# bb-8.net
KiCad netlist of a schematic drawn in EAGLE
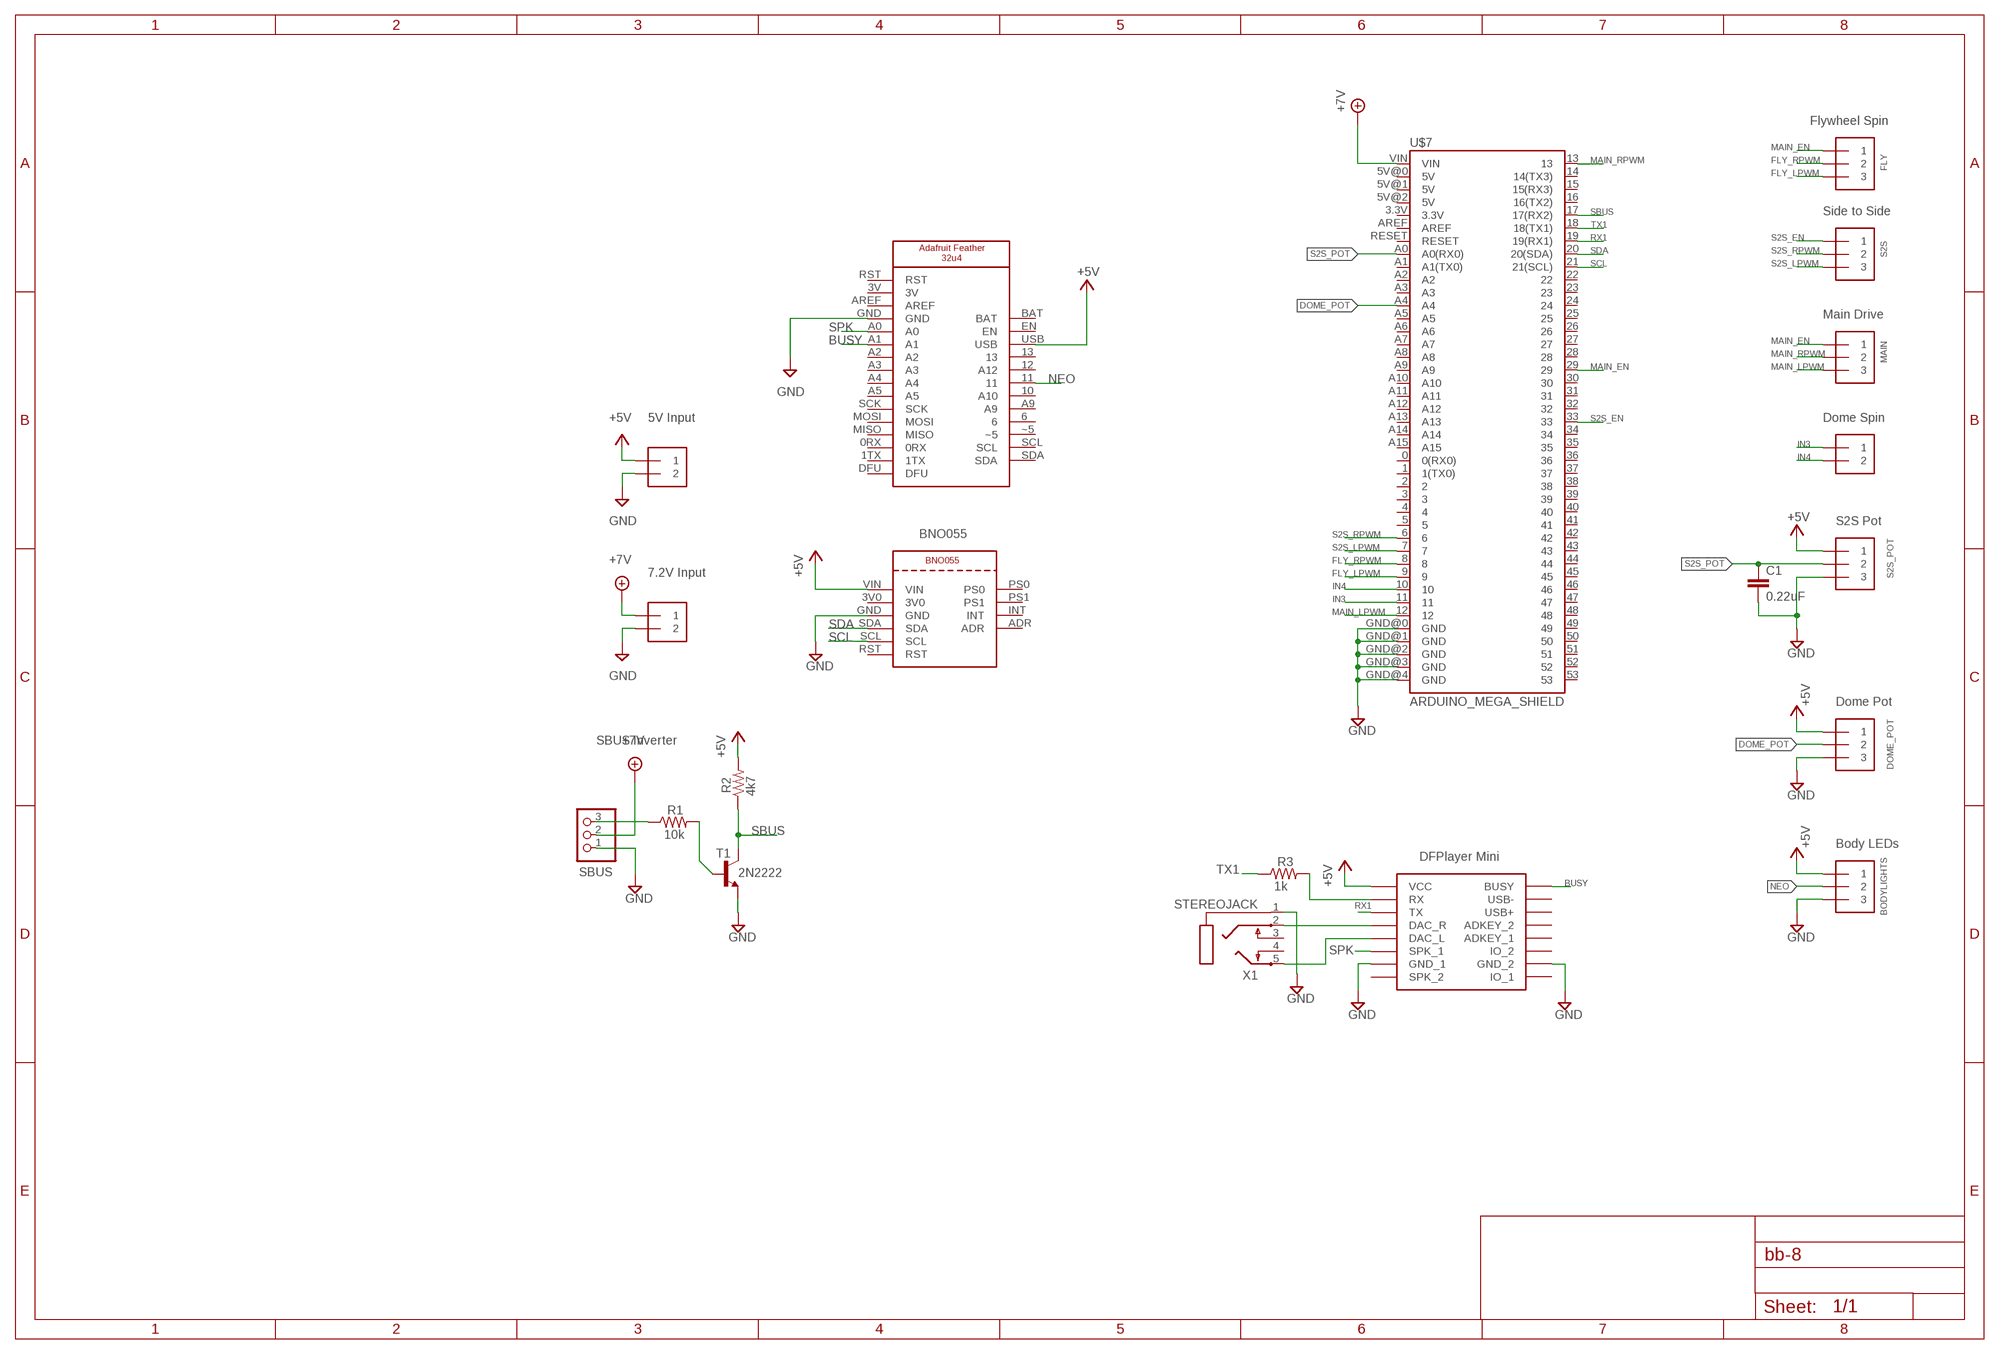
[diagram p0: schematic, sheet 1]

(export (version "E")
  (design (tool "Eeschema 10.0.6"))
  (components
    (comp (ref "5V")
      (value "1X2-3.5MM")
      (footprint "eagle-import:1X2-3.5MM")
      (libsource (lib "eagle-import") (part "1X2-3.5MM"))
    )
    (comp (ref "7V2")
      (value "1X2-3.5MM")
      (footprint "eagle-import:1X2-3.5MM")
      (libsource (lib "eagle-import") (part "1X2-3.5MM"))
    )
    (comp (ref "BODYLIGHTS")
      (value "SCREW_TERMINAL_3_PIN")
      (footprint "eagle-import:SCREW_TERMINAL_3_PIN")
      (libsource (lib "eagle-import") (part "SCREW_TERMINAL_3_PIN"))
    )
    (comp (ref "C1")
      (value "0.22uF")
      (footprint "eagle-import:C050-024X044")
      (libsource (lib "eagle-import") (part "C-EU050-024X044"))
    )
    (comp (ref "DOME")
      (value "1X2-3.5MM")
      (footprint "eagle-import:1X2-3.5MM")
      (libsource (lib "eagle-import") (part "1X2-3.5MM"))
    )
    (comp (ref "DOME_POT")
      (value "SCREW_TERMINAL_3_PIN")
      (footprint "eagle-import:SCREW_TERMINAL_3_PIN")
      (libsource (lib "eagle-import") (part "SCREW_TERMINAL_3_PIN"))
    )
    (comp (ref "FLY")
      (value "SCREW_TERMINAL_3_PIN")
      (footprint "eagle-import:SCREW_TERMINAL_3_PIN")
      (libsource (lib "eagle-import") (part "SCREW_TERMINAL_3_PIN"))
    )
    (comp (ref "MAIN")
      (value "SCREW_TERMINAL_3_PIN")
      (footprint "eagle-import:SCREW_TERMINAL_3_PIN")
      (libsource (lib "eagle-import") (part "SCREW_TERMINAL_3_PIN"))
    )
    (comp (ref "R1")
      (value "10k")
      (footprint "eagle-import:0204_7")
      (libsource (lib "eagle-import") (part "R-US_0204/7"))
    )
    (comp (ref "R2")
      (value "4k7")
      (footprint "eagle-import:0204_7")
      (libsource (lib "eagle-import") (part "R-US_0204/7"))
    )
    (comp (ref "R3")
      (value "1k")
      (footprint "eagle-import:0204_7")
      (libsource (lib "eagle-import") (part "R-US_0204/7"))
    )
    (comp (ref "S2S")
      (value "SCREW_TERMINAL_3_PIN")
      (footprint "eagle-import:SCREW_TERMINAL_3_PIN")
      (libsource (lib "eagle-import") (part "SCREW_TERMINAL_3_PIN"))
    )
    (comp (ref "S2S_POT")
      (value "SCREW_TERMINAL_3_PIN")
      (footprint "eagle-import:SCREW_TERMINAL_3_PIN")
      (libsource (lib "eagle-import") (part "SCREW_TERMINAL_3_PIN"))
    )
    (comp (ref "SBUS")
      (value "PINHD-1X3")
      (footprint "eagle-import:1X03")
      (libsource (lib "eagle-import") (part "PINHD-1X3"))
    )
    (comp (ref "T1")
      (value "2N2222")
      (footprint "eagle-import:TO92-EBC-OVAL")
      (libsource (lib "eagle-import") (part "2N2222"))
    )
    (comp (ref "U$1")
      (value "DFPLAYER")
      (footprint "eagle-import:DFPLAYER")
      (libsource (lib "eagle-import") (part "DFPLAYER"))
    )
    (comp (ref "U$2")
      (value "ADAFRUIT_BNO055")
      (footprint "eagle-import:ADAFRUIT_BNO055")
      (libsource (lib "eagle-import") (part "ADAFRUIT_BNO055"))
    )
    (comp (ref "U$3")
      (value "ADAFRUIT_FEATHER_32U4")
      (footprint "eagle-import:ADAFRUIT_FEATHER_32U4")
      (libsource (lib "eagle-import") (part "ADAFRUIT_FEATHER_32U4"))
    )
    (comp (ref "U$7")
      (value "ARDUINO_MEGA_SHIELD")
      (footprint "eagle-import:ARDUINO_MEGA_SHIELD")
      (libsource (lib "eagle-import") (part "ARDUINO_MEGA_SHIELD"))
    )
    (comp (ref "X1")
      (value "STEREOJACK")
      (footprint "eagle-import:STX3100")
      (libsource (lib "eagle-import") (part "STEREOJACK"))
    )
  )
  (nets
    (net (code "1") (name "+5V") (class "Default")
      (node (ref "5V") (pin "1") (pinfunction "1_1") (pintype "passive"))
      (node (ref "BODYLIGHTS") (pin "1") (pinfunction "1_1") (pintype "bidirectional"))
      (node (ref "DOME_POT") (pin "1") (pinfunction "1_1") (pintype "bidirectional"))
      (node (ref "R2") (pin "2") (pinfunction "2_2") (pintype "passive"))
      (node (ref "S2S_POT") (pin "1") (pinfunction "1_1") (pintype "bidirectional"))
      (node (ref "U$1") (pin "VCC") (pinfunction "VCC_VCC") (pintype "bidirectional"))
      (node (ref "U$2") (pin "VIN") (pinfunction "VIN_VIN") (pintype "bidirectional"))
      (node (ref "U$3") (pin "USB") (pinfunction "USB_USB") (pintype "bidirectional"))
    )
    (net (code "2") (name "+7V") (class "Default")
      (node (ref "7V2") (pin "1") (pinfunction "1_1") (pintype "passive"))
      (node (ref "SBUS") (pin "2") (pinfunction "2_2") (pintype "passive"))
      (node (ref "U$7") (pin "VIN") (pinfunction "VIN_VIN") (pintype "bidirectional"))
    )
    (net (code "3") (name "/BUSY") (class "Default")
      (node (ref "U$1") (pin "BUSY") (pinfunction "BUSY_BUSY") (pintype "bidirectional"))
      (node (ref "U$3") (pin "A1") (pinfunction "A1_A1") (pintype "bidirectional"))
    )
    (net (code "4") (name "/FLY_LPWM") (class "Default")
      (node (ref "FLY") (pin "3") (pinfunction "3_3") (pintype "bidirectional"))
      (node (ref "U$7") (pin "9") (pinfunction "9_9") (pintype "bidirectional"))
    )
    (net (code "5") (name "/FLY_RPWM") (class "Default")
      (node (ref "FLY") (pin "2") (pinfunction "2_2") (pintype "bidirectional"))
      (node (ref "U$7") (pin "8") (pinfunction "8_8") (pintype "bidirectional"))
    )
    (net (code "6") (name "/IN3") (class "Default")
      (node (ref "DOME") (pin "1") (pinfunction "1_1") (pintype "passive"))
      (node (ref "U$7") (pin "11") (pinfunction "11_11") (pintype "bidirectional"))
    )
    (net (code "7") (name "/IN4") (class "Default")
      (node (ref "DOME") (pin "2") (pinfunction "2_2") (pintype "passive"))
      (node (ref "U$7") (pin "10") (pinfunction "10_10") (pintype "bidirectional"))
    )
    (net (code "8") (name "/MAIN_EN") (class "Default")
      (node (ref "FLY") (pin "1") (pinfunction "1_1") (pintype "bidirectional"))
      (node (ref "MAIN") (pin "1") (pinfunction "1_1") (pintype "bidirectional"))
      (node (ref "U$7") (pin "29") (pinfunction "29_29") (pintype "bidirectional"))
    )
    (net (code "9") (name "/MAIN_LPWM") (class "Default")
      (node (ref "MAIN") (pin "3") (pinfunction "3_3") (pintype "bidirectional"))
      (node (ref "U$7") (pin "12") (pinfunction "12_12") (pintype "bidirectional"))
    )
    (net (code "10") (name "/MAIN_RPWM") (class "Default")
      (node (ref "MAIN") (pin "2") (pinfunction "2_2") (pintype "bidirectional"))
      (node (ref "U$7") (pin "13") (pinfunction "13_13") (pintype "bidirectional"))
    )
    (net (code "11") (name "/RX1") (class "Default")
      (node (ref "U$1") (pin "TX") (pinfunction "TX_TX") (pintype "bidirectional"))
      (node (ref "U$7") (pin "19") (pinfunction "19(RX1)_19") (pintype "bidirectional"))
    )
    (net (code "12") (name "/S2S_EN") (class "Default")
      (node (ref "S2S") (pin "1") (pinfunction "1_1") (pintype "bidirectional"))
      (node (ref "U$7") (pin "33") (pinfunction "33_33") (pintype "bidirectional"))
    )
    (net (code "13") (name "/S2S_LPWM") (class "Default")
      (node (ref "S2S") (pin "3") (pinfunction "3_3") (pintype "bidirectional"))
      (node (ref "U$7") (pin "7") (pinfunction "7_7") (pintype "bidirectional"))
    )
    (net (code "14") (name "/S2S_RPWM") (class "Default")
      (node (ref "S2S") (pin "2") (pinfunction "2_2") (pintype "bidirectional"))
      (node (ref "U$7") (pin "6") (pinfunction "6_6") (pintype "bidirectional"))
    )
    (net (code "15") (name "/SBUS") (class "Default")
      (node (ref "R2") (pin "1") (pinfunction "1_1") (pintype "passive"))
      (node (ref "T1") (pin "C") (pinfunction "C_C") (pintype "passive"))
      (node (ref "U$7") (pin "17") (pinfunction "17(RX2)_17") (pintype "bidirectional"))
    )
    (net (code "16") (name "/SCL") (class "Default")
      (node (ref "U$2") (pin "SCL") (pinfunction "SCL_SCL") (pintype "bidirectional"))
      (node (ref "U$7") (pin "21") (pinfunction "21(SCL)_21") (pintype "bidirectional"))
    )
    (net (code "17") (name "/SDA") (class "Default")
      (node (ref "U$2") (pin "SDA") (pinfunction "SDA_SDA") (pintype "bidirectional"))
      (node (ref "U$7") (pin "20") (pinfunction "20(SDA)_20") (pintype "bidirectional"))
    )
    (net (code "18") (name "/SPK") (class "Default")
      (node (ref "U$1") (pin "SPK1") (pinfunction "SPK_1_SPK1") (pintype "bidirectional"))
      (node (ref "U$3") (pin "A0") (pinfunction "A0_A0") (pintype "bidirectional"))
    )
    (net (code "19") (name "/TX1") (class "Default")
      (node (ref "R3") (pin "1") (pinfunction "1_1") (pintype "passive"))
      (node (ref "U$7") (pin "18") (pinfunction "18(TX1)_18") (pintype "bidirectional"))
    )
    (net (code "20") (name "DOME_POT") (class "Default")
      (node (ref "DOME_POT") (pin "2") (pinfunction "2_2") (pintype "bidirectional"))
      (node (ref "U$7") (pin "A4") (pinfunction "A4_A4") (pintype "bidirectional"))
    )
    (net (code "21") (name "GND") (class "Default")
      (node (ref "5V") (pin "2") (pinfunction "2_2") (pintype "passive"))
      (node (ref "7V2") (pin "2") (pinfunction "2_2") (pintype "passive"))
      (node (ref "BODYLIGHTS") (pin "3") (pinfunction "3_3") (pintype "bidirectional"))
      (node (ref "C1") (pin "2") (pinfunction "2_2") (pintype "passive"))
      (node (ref "DOME_POT") (pin "3") (pinfunction "3_3") (pintype "bidirectional"))
      (node (ref "S2S_POT") (pin "3") (pinfunction "3_3") (pintype "bidirectional"))
      (node (ref "SBUS") (pin "1") (pinfunction "1_1") (pintype "passive"))
      (node (ref "T1") (pin "E") (pinfunction "E_E") (pintype "passive"))
      (node (ref "U$1") (pin "GND_1") (pinfunction "GND_1_GND_1") (pintype "bidirectional"))
      (node (ref "U$1") (pin "GND_2") (pinfunction "GND_2_GND_2") (pintype "bidirectional"))
      (node (ref "U$2") (pin "GND") (pinfunction "GND_GND") (pintype "bidirectional"))
      (node (ref "U$3") (pin "GND") (pinfunction "GND_GND") (pintype "bidirectional"))
      (node (ref "U$7") (pin "GND@0") (pinfunction "GND_GND@0") (pintype "bidirectional"))
      (node (ref "U$7") (pin "GND@1") (pinfunction "GND_GND@1") (pintype "bidirectional"))
      (node (ref "U$7") (pin "GND@2") (pinfunction "GND_GND@2") (pintype "bidirectional"))
      (node (ref "U$7") (pin "GND@3") (pinfunction "GND_GND@3") (pintype "bidirectional"))
      (node (ref "U$7") (pin "GND@4") (pinfunction "GND_GND@4") (pintype "bidirectional"))
      (node (ref "X1") (pin "1") (pinfunction "1_1") (pintype "passive"))
    )
    (net (code "22") (name "NEO") (class "Default")
      (node (ref "BODYLIGHTS") (pin "2") (pinfunction "2_2") (pintype "bidirectional"))
      (node (ref "U$3") (pin "11") (pinfunction "11_11") (pintype "bidirectional"))
    )
    (net (code "23") (name "Net-(R1-Pad1)") (class "Default")
      (node (ref "R1") (pin "1") (pinfunction "1_1") (pintype "passive"))
      (node (ref "SBUS") (pin "3") (pinfunction "3_3") (pintype "passive"))
    )
    (net (code "24") (name "Net-(R1-Pad2)") (class "Default")
      (node (ref "R1") (pin "2") (pinfunction "2_2") (pintype "passive"))
      (node (ref "T1") (pin "B") (pinfunction "B_B") (pintype "passive"))
    )
    (net (code "25") (name "Net-(R3-Pad2)") (class "Default")
      (node (ref "R3") (pin "2") (pinfunction "2_2") (pintype "passive"))
      (node (ref "U$1") (pin "RX") (pinfunction "RX_RX") (pintype "bidirectional"))
    )
    (net (code "26") (name "Net-(U$1-PadDAC_L)") (class "Default")
      (node (ref "U$1") (pin "DAC_L") (pinfunction "DAC_L_DAC_L") (pintype "bidirectional"))
      (node (ref "X1") (pin "5") (pinfunction "5_5") (pintype "passive"))
    )
    (net (code "27") (name "Net-(U$1-PadDAC_R)") (class "Default")
      (node (ref "U$1") (pin "DAC_R") (pinfunction "DAC_R_DAC_R") (pintype "bidirectional"))
      (node (ref "X1") (pin "2") (pinfunction "2_2") (pintype "passive"))
    )
    (net (code "28") (name "S2S_POT") (class "Default")
      (node (ref "C1") (pin "1") (pinfunction "1_1") (pintype "passive"))
      (node (ref "S2S_POT") (pin "2") (pinfunction "2_2") (pintype "bidirectional"))
      (node (ref "U$7") (pin "A0") (pinfunction "A0(RX0)_A0") (pintype "bidirectional"))
    )
    (net (code "29") (name "unconnected-(U$1-ADKEY_1-PadADKEY1)") (class "Default")
      (node (ref "U$1") (pin "ADKEY1") (pinfunction "ADKEY_1_ADKEY1") (pintype "bidirectional"))
    )
    (net (code "30") (name "unconnected-(U$1-ADKEY_2-PadADKEY2)") (class "Default")
      (node (ref "U$1") (pin "ADKEY2") (pinfunction "ADKEY_2_ADKEY2") (pintype "bidirectional"))
    )
    (net (code "31") (name "unconnected-(U$1-IO_1-PadIO1)") (class "Default")
      (node (ref "U$1") (pin "IO1") (pinfunction "IO_1_IO1") (pintype "bidirectional"))
    )
    (net (code "32") (name "unconnected-(U$1-IO_2-PadIO2)") (class "Default")
      (node (ref "U$1") (pin "IO2") (pinfunction "IO_2_IO2") (pintype "bidirectional"))
    )
    (net (code "33") (name "unconnected-(U$1-PadUSB+)") (class "Default")
      (node (ref "U$1") (pin "USB+") (pinfunction "USB+_USB+") (pintype "bidirectional"))
    )
    (net (code "34") (name "unconnected-(U$1-PadUSB-)") (class "Default")
      (node (ref "U$1") (pin "USB-") (pinfunction "USB-_USB-") (pintype "bidirectional"))
    )
    (net (code "35") (name "unconnected-(U$1-SPK_2-PadSPK2)") (class "Default")
      (node (ref "U$1") (pin "SPK2") (pinfunction "SPK_2_SPK2") (pintype "bidirectional"))
    )
    (net (code "36") (name "unconnected-(U$2-Pad3V0)") (class "Default")
      (node (ref "U$2") (pin "3V0") (pinfunction "3V0_3V0") (pintype "bidirectional"))
    )
    (net (code "37") (name "unconnected-(U$2-PadADR)") (class "Default")
      (node (ref "U$2") (pin "ADR") (pinfunction "ADR_ADR") (pintype "bidirectional"))
    )
    (net (code "38") (name "unconnected-(U$2-PadINT)") (class "Default")
      (node (ref "U$2") (pin "INT") (pinfunction "INT_INT") (pintype "bidirectional"))
    )
    (net (code "39") (name "unconnected-(U$2-PadPS0)") (class "Default")
      (node (ref "U$2") (pin "PS0") (pinfunction "PS0_PS0") (pintype "bidirectional"))
    )
    (net (code "40") (name "unconnected-(U$2-PadPS1)") (class "Default")
      (node (ref "U$2") (pin "PS1") (pinfunction "PS1_PS1") (pintype "bidirectional"))
    )
    (net (code "41") (name "unconnected-(U$2-PadRST)") (class "Default")
      (node (ref "U$2") (pin "RST") (pinfunction "RST_RST") (pintype "bidirectional"))
    )
    (net (code "42") (name "unconnected-(U$3-A10-Pad10)") (class "Default")
      (node (ref "U$3") (pin "10") (pinfunction "A10_10") (pintype "bidirectional"))
    )
    (net (code "43") (name "unconnected-(U$3-A12-Pad12)") (class "Default")
      (node (ref "U$3") (pin "12") (pinfunction "A12_12") (pintype "bidirectional"))
    )
    (net (code "44") (name "unconnected-(U$3-Pad0RX)") (class "Default")
      (node (ref "U$3") (pin "0RX") (pinfunction "0RX_0RX") (pintype "bidirectional"))
    )
    (net (code "45") (name "unconnected-(U$3-Pad1TX)") (class "Default")
      (node (ref "U$3") (pin "1TX") (pinfunction "1TX_1TX") (pintype "bidirectional"))
    )
    (net (code "46") (name "unconnected-(U$3-Pad3V)") (class "Default")
      (node (ref "U$3") (pin "3V") (pinfunction "3V_3V") (pintype "bidirectional"))
    )
    (net (code "47") (name "unconnected-(U$3-Pad6)") (class "Default")
      (node (ref "U$3") (pin "6") (pinfunction "6_6") (pintype "bidirectional"))
    )
    (net (code "48") (name "unconnected-(U$3-Pad13)") (class "Default")
      (node (ref "U$3") (pin "13") (pinfunction "13_13") (pintype "bidirectional"))
    )
    (net (code "49") (name "unconnected-(U$3-PadA2)") (class "Default")
      (node (ref "U$3") (pin "A2") (pinfunction "A2_A2") (pintype "bidirectional"))
    )
    (net (code "50") (name "unconnected-(U$3-PadA3)") (class "Default")
      (node (ref "U$3") (pin "A3") (pinfunction "A3_A3") (pintype "bidirectional"))
    )
    (net (code "51") (name "unconnected-(U$3-PadA4)") (class "Default")
      (node (ref "U$3") (pin "A4") (pinfunction "A4_A4") (pintype "bidirectional"))
    )
    (net (code "52") (name "unconnected-(U$3-PadA5)") (class "Default")
      (node (ref "U$3") (pin "A5") (pinfunction "A5_A5") (pintype "bidirectional"))
    )
    (net (code "53") (name "unconnected-(U$3-PadA9)") (class "Default")
      (node (ref "U$3") (pin "A9") (pinfunction "A9_A9") (pintype "bidirectional"))
    )
    (net (code "54") (name "unconnected-(U$3-PadAREF)") (class "Default")
      (node (ref "U$3") (pin "AREF") (pinfunction "AREF_AREF") (pintype "bidirectional"))
    )
    (net (code "55") (name "unconnected-(U$3-PadBAT)") (class "Default")
      (node (ref "U$3") (pin "BAT") (pinfunction "BAT_BAT") (pintype "bidirectional"))
    )
    (net (code "56") (name "unconnected-(U$3-PadDFU)") (class "Default")
      (node (ref "U$3") (pin "DFU") (pinfunction "DFU_DFU") (pintype "bidirectional"))
    )
    (net (code "57") (name "unconnected-(U$3-PadEN)") (class "Default")
      (node (ref "U$3") (pin "EN") (pinfunction "EN_EN") (pintype "bidirectional"))
    )
    (net (code "58") (name "unconnected-(U$3-PadMISO)") (class "Default")
      (node (ref "U$3") (pin "MISO") (pinfunction "MISO_MISO") (pintype "bidirectional"))
    )
    (net (code "59") (name "unconnected-(U$3-PadMOSI)") (class "Default")
      (node (ref "U$3") (pin "MOSI") (pinfunction "MOSI_MOSI") (pintype "bidirectional"))
    )
    (net (code "60") (name "unconnected-(U$3-PadRST)") (class "Default")
      (node (ref "U$3") (pin "RST") (pinfunction "RST_RST") (pintype "bidirectional"))
    )
    (net (code "61") (name "unconnected-(U$3-PadSCK)") (class "Default")
      (node (ref "U$3") (pin "SCK") (pinfunction "SCK_SCK") (pintype "bidirectional"))
    )
    (net (code "62") (name "unconnected-(U$3-PadSCL)") (class "Default")
      (node (ref "U$3") (pin "SCL") (pinfunction "SCL_SCL") (pintype "bidirectional"))
    )
    (net (code "63") (name "unconnected-(U$3-PadSDA)") (class "Default")
      (node (ref "U$3") (pin "SDA") (pinfunction "SDA_SDA") (pintype "bidirectional"))
    )
    (net (code "64") (name "unconnected-(U$3-~{5}-Pad~5)") (class "Default")
      (node (ref "U$3") (pin "~5") (pinfunction "~{5}_~5") (pintype "bidirectional"))
    )
    (net (code "65") (name "unconnected-(U$7-0(RX0)-Pad0)") (class "Default")
      (node (ref "U$7") (pin "0") (pinfunction "0(RX0)_0") (pintype "bidirectional"))
    )
    (net (code "66") (name "unconnected-(U$7-1(TX0)-Pad1)") (class "Default")
      (node (ref "U$7") (pin "1") (pinfunction "1(TX0)_1") (pintype "bidirectional"))
    )
    (net (code "67") (name "unconnected-(U$7-5V-Pad5V@0)") (class "Default")
      (node (ref "U$7") (pin "5V@0") (pinfunction "5V_5V@0") (pintype "bidirectional"))
    )
    (net (code "68") (name "unconnected-(U$7-5V-Pad5V@1)") (class "Default")
      (node (ref "U$7") (pin "5V@1") (pinfunction "5V_5V@1") (pintype "bidirectional"))
    )
    (net (code "69") (name "unconnected-(U$7-5V-Pad5V@2)") (class "Default")
      (node (ref "U$7") (pin "5V@2") (pinfunction "5V_5V@2") (pintype "bidirectional"))
    )
    (net (code "70") (name "unconnected-(U$7-14(TX3)-Pad14)") (class "Default")
      (node (ref "U$7") (pin "14") (pinfunction "14(TX3)_14") (pintype "bidirectional"))
    )
    (net (code "71") (name "unconnected-(U$7-15(RX3)-Pad15)") (class "Default")
      (node (ref "U$7") (pin "15") (pinfunction "15(RX3)_15") (pintype "bidirectional"))
    )
    (net (code "72") (name "unconnected-(U$7-16(TX2)-Pad16)") (class "Default")
      (node (ref "U$7") (pin "16") (pinfunction "16(TX2)_16") (pintype "bidirectional"))
    )
    (net (code "73") (name "unconnected-(U$7-A1(TX0)-PadA1)") (class "Default")
      (node (ref "U$7") (pin "A1") (pinfunction "A1(TX0)_A1") (pintype "bidirectional"))
    )
    (net (code "74") (name "unconnected-(U$7-Pad2)") (class "Default")
      (node (ref "U$7") (pin "2") (pinfunction "2_2") (pintype "bidirectional"))
    )
    (net (code "75") (name "unconnected-(U$7-Pad3)") (class "Default")
      (node (ref "U$7") (pin "3") (pinfunction "3_3") (pintype "bidirectional"))
    )
    (net (code "76") (name "unconnected-(U$7-Pad3.3V)") (class "Default")
      (node (ref "U$7") (pin "3.3V") (pinfunction "3.3V_3.3V") (pintype "bidirectional"))
    )
    (net (code "77") (name "unconnected-(U$7-Pad4)") (class "Default")
      (node (ref "U$7") (pin "4") (pinfunction "4_4") (pintype "bidirectional"))
    )
    (net (code "78") (name "unconnected-(U$7-Pad5)") (class "Default")
      (node (ref "U$7") (pin "5") (pinfunction "5_5") (pintype "bidirectional"))
    )
    (net (code "79") (name "unconnected-(U$7-Pad22)") (class "Default")
      (node (ref "U$7") (pin "22") (pinfunction "22_22") (pintype "bidirectional"))
    )
    (net (code "80") (name "unconnected-(U$7-Pad23)") (class "Default")
      (node (ref "U$7") (pin "23") (pinfunction "23_23") (pintype "bidirectional"))
    )
    (net (code "81") (name "unconnected-(U$7-Pad24)") (class "Default")
      (node (ref "U$7") (pin "24") (pinfunction "24_24") (pintype "bidirectional"))
    )
    (net (code "82") (name "unconnected-(U$7-Pad25)") (class "Default")
      (node (ref "U$7") (pin "25") (pinfunction "25_25") (pintype "bidirectional"))
    )
    (net (code "83") (name "unconnected-(U$7-Pad26)") (class "Default")
      (node (ref "U$7") (pin "26") (pinfunction "26_26") (pintype "bidirectional"))
    )
    (net (code "84") (name "unconnected-(U$7-Pad27)") (class "Default")
      (node (ref "U$7") (pin "27") (pinfunction "27_27") (pintype "bidirectional"))
    )
    (net (code "85") (name "unconnected-(U$7-Pad28)") (class "Default")
      (node (ref "U$7") (pin "28") (pinfunction "28_28") (pintype "bidirectional"))
    )
    (net (code "86") (name "unconnected-(U$7-Pad30)") (class "Default")
      (node (ref "U$7") (pin "30") (pinfunction "30_30") (pintype "bidirectional"))
    )
    (net (code "87") (name "unconnected-(U$7-Pad31)") (class "Default")
      (node (ref "U$7") (pin "31") (pinfunction "31_31") (pintype "bidirectional"))
    )
    (net (code "88") (name "unconnected-(U$7-Pad32)") (class "Default")
      (node (ref "U$7") (pin "32") (pinfunction "32_32") (pintype "bidirectional"))
    )
    (net (code "89") (name "unconnected-(U$7-Pad34)") (class "Default")
      (node (ref "U$7") (pin "34") (pinfunction "34_34") (pintype "bidirectional"))
    )
    (net (code "90") (name "unconnected-(U$7-Pad35)") (class "Default")
      (node (ref "U$7") (pin "35") (pinfunction "35_35") (pintype "bidirectional"))
    )
    (net (code "91") (name "unconnected-(U$7-Pad36)") (class "Default")
      (node (ref "U$7") (pin "36") (pinfunction "36_36") (pintype "bidirectional"))
    )
    (net (code "92") (name "unconnected-(U$7-Pad37)") (class "Default")
      (node (ref "U$7") (pin "37") (pinfunction "37_37") (pintype "bidirectional"))
    )
    (net (code "93") (name "unconnected-(U$7-Pad38)") (class "Default")
      (node (ref "U$7") (pin "38") (pinfunction "38_38") (pintype "bidirectional"))
    )
    (net (code "94") (name "unconnected-(U$7-Pad39)") (class "Default")
      (node (ref "U$7") (pin "39") (pinfunction "39_39") (pintype "bidirectional"))
    )
    (net (code "95") (name "unconnected-(U$7-Pad40)") (class "Default")
      (node (ref "U$7") (pin "40") (pinfunction "40_40") (pintype "bidirectional"))
    )
    (net (code "96") (name "unconnected-(U$7-Pad41)") (class "Default")
      (node (ref "U$7") (pin "41") (pinfunction "41_41") (pintype "bidirectional"))
    )
    (net (code "97") (name "unconnected-(U$7-Pad42)") (class "Default")
      (node (ref "U$7") (pin "42") (pinfunction "42_42") (pintype "bidirectional"))
    )
    (net (code "98") (name "unconnected-(U$7-Pad43)") (class "Default")
      (node (ref "U$7") (pin "43") (pinfunction "43_43") (pintype "bidirectional"))
    )
    (net (code "99") (name "unconnected-(U$7-Pad44)") (class "Default")
      (node (ref "U$7") (pin "44") (pinfunction "44_44") (pintype "bidirectional"))
    )
    (net (code "100") (name "unconnected-(U$7-Pad45)") (class "Default")
      (node (ref "U$7") (pin "45") (pinfunction "45_45") (pintype "bidirectional"))
    )
    (net (code "101") (name "unconnected-(U$7-Pad46)") (class "Default")
      (node (ref "U$7") (pin "46") (pinfunction "46_46") (pintype "bidirectional"))
    )
    (net (code "102") (name "unconnected-(U$7-Pad47)") (class "Default")
      (node (ref "U$7") (pin "47") (pinfunction "47_47") (pintype "bidirectional"))
    )
    (net (code "103") (name "unconnected-(U$7-Pad48)") (class "Default")
      (node (ref "U$7") (pin "48") (pinfunction "48_48") (pintype "bidirectional"))
    )
    (net (code "104") (name "unconnected-(U$7-Pad49)") (class "Default")
      (node (ref "U$7") (pin "49") (pinfunction "49_49") (pintype "bidirectional"))
    )
    (net (code "105") (name "unconnected-(U$7-Pad50)") (class "Default")
      (node (ref "U$7") (pin "50") (pinfunction "50_50") (pintype "bidirectional"))
    )
    (net (code "106") (name "unconnected-(U$7-Pad51)") (class "Default")
      (node (ref "U$7") (pin "51") (pinfunction "51_51") (pintype "bidirectional"))
    )
    (net (code "107") (name "unconnected-(U$7-Pad52)") (class "Default")
      (node (ref "U$7") (pin "52") (pinfunction "52_52") (pintype "bidirectional"))
    )
    (net (code "108") (name "unconnected-(U$7-Pad53)") (class "Default")
      (node (ref "U$7") (pin "53") (pinfunction "53_53") (pintype "bidirectional"))
    )
    (net (code "109") (name "unconnected-(U$7-PadA2)") (class "Default")
      (node (ref "U$7") (pin "A2") (pinfunction "A2_A2") (pintype "bidirectional"))
    )
    (net (code "110") (name "unconnected-(U$7-PadA3)") (class "Default")
      (node (ref "U$7") (pin "A3") (pinfunction "A3_A3") (pintype "bidirectional"))
    )
    (net (code "111") (name "unconnected-(U$7-PadA5)") (class "Default")
      (node (ref "U$7") (pin "A5") (pinfunction "A5_A5") (pintype "bidirectional"))
    )
    (net (code "112") (name "unconnected-(U$7-PadA6)") (class "Default")
      (node (ref "U$7") (pin "A6") (pinfunction "A6_A6") (pintype "bidirectional"))
    )
    (net (code "113") (name "unconnected-(U$7-PadA7)") (class "Default")
      (node (ref "U$7") (pin "A7") (pinfunction "A7_A7") (pintype "bidirectional"))
    )
    (net (code "114") (name "unconnected-(U$7-PadA8)") (class "Default")
      (node (ref "U$7") (pin "A8") (pinfunction "A8_A8") (pintype "bidirectional"))
    )
    (net (code "115") (name "unconnected-(U$7-PadA9)") (class "Default")
      (node (ref "U$7") (pin "A9") (pinfunction "A9_A9") (pintype "bidirectional"))
    )
    (net (code "116") (name "unconnected-(U$7-PadA10)") (class "Default")
      (node (ref "U$7") (pin "A10") (pinfunction "A10_A10") (pintype "bidirectional"))
    )
    (net (code "117") (name "unconnected-(U$7-PadA11)") (class "Default")
      (node (ref "U$7") (pin "A11") (pinfunction "A11_A11") (pintype "bidirectional"))
    )
    (net (code "118") (name "unconnected-(U$7-PadA12)") (class "Default")
      (node (ref "U$7") (pin "A12") (pinfunction "A12_A12") (pintype "bidirectional"))
    )
    (net (code "119") (name "unconnected-(U$7-PadA13)") (class "Default")
      (node (ref "U$7") (pin "A13") (pinfunction "A13_A13") (pintype "bidirectional"))
    )
    (net (code "120") (name "unconnected-(U$7-PadA14)") (class "Default")
      (node (ref "U$7") (pin "A14") (pinfunction "A14_A14") (pintype "bidirectional"))
    )
    (net (code "121") (name "unconnected-(U$7-PadA15)") (class "Default")
      (node (ref "U$7") (pin "A15") (pinfunction "A15_A15") (pintype "bidirectional"))
    )
    (net (code "122") (name "unconnected-(U$7-PadAREF)") (class "Default")
      (node (ref "U$7") (pin "AREF") (pinfunction "AREF_AREF") (pintype "bidirectional"))
    )
    (net (code "123") (name "unconnected-(U$7-PadRESET)") (class "Default")
      (node (ref "U$7") (pin "RESET") (pinfunction "RESET_RESET") (pintype "bidirectional"))
    )
    (net (code "124") (name "unconnected-(X1-Pad3)") (class "Default")
      (node (ref "X1") (pin "3") (pinfunction "3_3") (pintype "passive"))
    )
    (net (code "125") (name "unconnected-(X1-Pad4)") (class "Default")
      (node (ref "X1") (pin "4") (pinfunction "4_4") (pintype "passive"))
    )
  )
)
